# Bandage_FPC.net
KiCad netlist of a schematic drawn in EAGLE
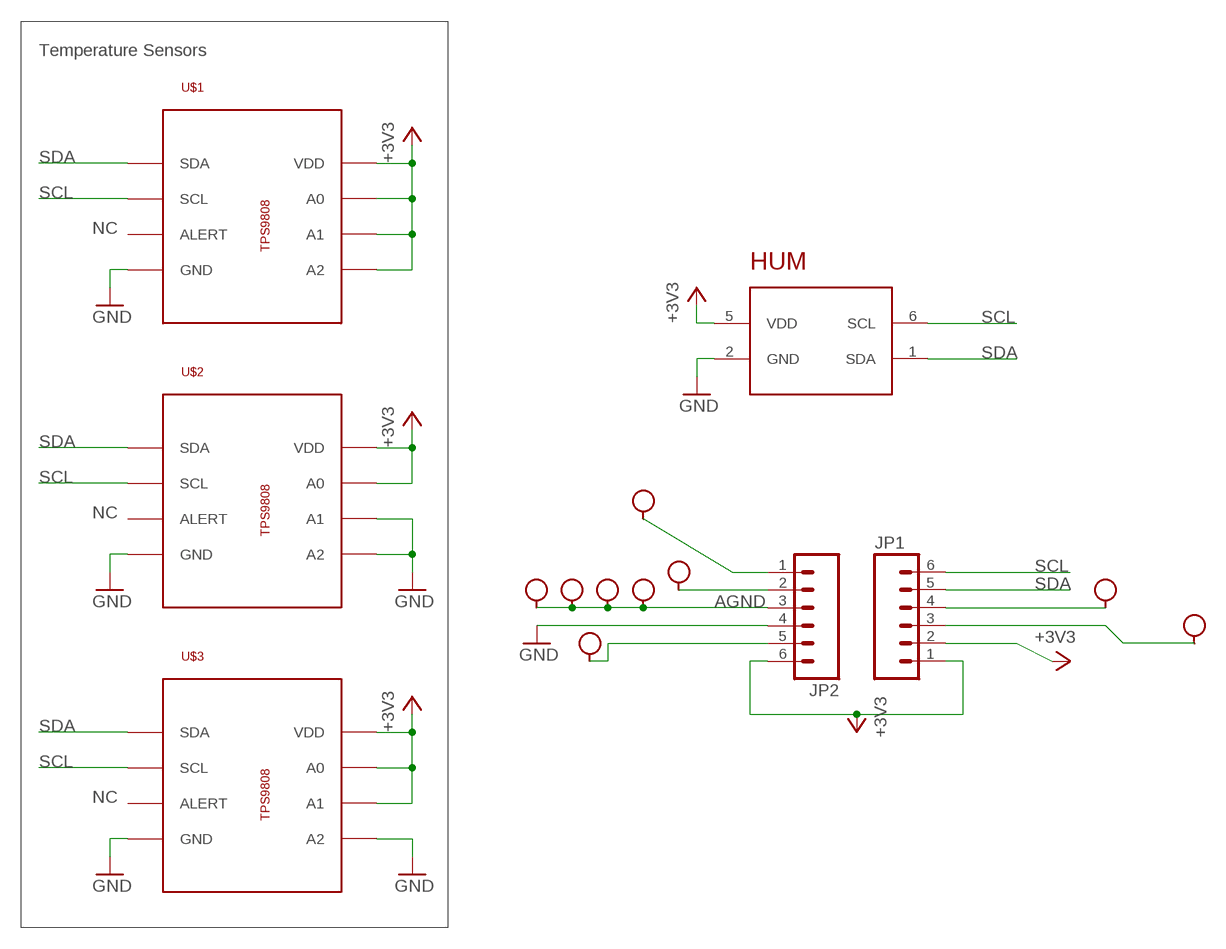
[diagram p0: schematic, sheet 1]

(export (version "E")
  (design (tool "Eeschema 10.0.6"))
  (components
    (comp (ref "H1")
      (value "SEW_HOLE-SMALL")
      (footprint "eagle-import:SIMPLE_HOLE_SM")
      (libsource (lib "eagle-import") (part "SEW_HOLE-SMALL"))
    )
    (comp (ref "H2")
      (value "SEW_HOLE-SMALL")
      (footprint "eagle-import:SIMPLE_HOLE_SM")
      (libsource (lib "eagle-import") (part "SEW_HOLE-SMALL"))
    )
    (comp (ref "H3")
      (value "SEW_HOLE-SMALL")
      (footprint "eagle-import:SIMPLE_HOLE_SM")
      (libsource (lib "eagle-import") (part "SEW_HOLE-SMALL"))
    )
    (comp (ref "H4")
      (value "SEW_HOLE-SMALL")
      (footprint "eagle-import:SIMPLE_HOLE_SM")
      (libsource (lib "eagle-import") (part "SEW_HOLE-SMALL"))
    )
    (comp (ref "H5")
      (value "SEW_HOLE-SMALL")
      (footprint "eagle-import:SIMPLE_HOLE_SM")
      (libsource (lib "eagle-import") (part "SEW_HOLE-SMALL"))
    )
    (comp (ref "H6")
      (value "SEW_HOLE-SMALL")
      (footprint "eagle-import:SIMPLE_HOLE_SM")
      (libsource (lib "eagle-import") (part "SEW_HOLE-SMALL"))
    )
    (comp (ref "H7")
      (value "SEW_HOLE-SMALL")
      (footprint "eagle-import:SIMPLE_HOLE_SM")
      (libsource (lib "eagle-import") (part "SEW_HOLE-SMALL"))
    )
    (comp (ref "H8")
      (value "SEW_HOLE-SMALL")
      (footprint "eagle-import:SIMPLE_HOLE_SM")
      (libsource (lib "eagle-import") (part "SEW_HOLE-SMALL"))
    )
    (comp (ref "H9")
      (value "SEW_HOLE-SMALL")
      (footprint "eagle-import:SIMPLE_HOLE_SM")
      (libsource (lib "eagle-import") (part "SEW_HOLE-SMALL"))
    )
    (comp (ref "HUM")
      (value "HDC1050")
      (footprint "eagle-import:SON-6")
      (libsource (lib "eagle-import") (part "HDC1050"))
    )
    (comp (ref "JP1")
      (value "M06LOCK")
      (footprint "eagle-import:1X06_LOCK")
      (libsource (lib "eagle-import") (part "M06LOCK"))
    )
    (comp (ref "JP2")
      (value "M06LOCK")
      (footprint "eagle-import:1X06_LOCK")
      (libsource (lib "eagle-import") (part "M06LOCK"))
    )
    (comp (ref "U$1")
      (value "MCP9808")
      (footprint "eagle-import:MSOP8")
      (libsource (lib "eagle-import") (part "MCP9808"))
    )
    (comp (ref "U$2")
      (value "MCP9808")
      (footprint "eagle-import:MSOP8")
      (libsource (lib "eagle-import") (part "MCP9808"))
    )
    (comp (ref "U$3")
      (value "MCP9808")
      (footprint "eagle-import:MSOP8")
      (libsource (lib "eagle-import") (part "MCP9808"))
    )
  )
  (nets
    (net (code "1") (name "+3V3") (class "Default")
      (node (ref "HUM") (pin "5") (pinfunction "VDD_5") (pintype "bidirectional"))
      (node (ref "JP1") (pin "1") (pinfunction "1_1") (pintype "passive"))
      (node (ref "JP1") (pin "2") (pinfunction "2_2") (pintype "passive"))
      (node (ref "JP2") (pin "6") (pinfunction "6_6") (pintype "passive"))
      (node (ref "U$1") (pin "5") (pinfunction "A2_5") (pintype "bidirectional"))
      (node (ref "U$1") (pin "6") (pinfunction "A1_6") (pintype "bidirectional"))
      (node (ref "U$1") (pin "7") (pinfunction "A0_7") (pintype "bidirectional"))
      (node (ref "U$1") (pin "8") (pinfunction "VDD_8") (pintype "bidirectional"))
      (node (ref "U$2") (pin "7") (pinfunction "A0_7") (pintype "bidirectional"))
      (node (ref "U$2") (pin "8") (pinfunction "VDD_8") (pintype "bidirectional"))
      (node (ref "U$3") (pin "6") (pinfunction "A1_6") (pintype "bidirectional"))
      (node (ref "U$3") (pin "7") (pinfunction "A0_7") (pintype "bidirectional"))
      (node (ref "U$3") (pin "8") (pinfunction "VDD_8") (pintype "bidirectional"))
    )
    (net (code "2") (name "/AGND") (class "Default")
      (node (ref "H6") (pin "P$1") (pinfunction "P$1_P$1") (pintype "bidirectional"))
      (node (ref "H7") (pin "P$1") (pinfunction "P$1_P$1") (pintype "bidirectional"))
      (node (ref "H8") (pin "P$1") (pinfunction "P$1_P$1") (pintype "bidirectional"))
      (node (ref "H9") (pin "P$1") (pinfunction "P$1_P$1") (pintype "bidirectional"))
      (node (ref "JP2") (pin "3") (pinfunction "3_3") (pintype "passive"))
    )
    (net (code "3") (name "/SCL") (class "Default")
      (node (ref "HUM") (pin "6") (pinfunction "SCL_6") (pintype "bidirectional"))
      (node (ref "JP1") (pin "6") (pinfunction "6_6") (pintype "passive"))
      (node (ref "U$1") (pin "2") (pinfunction "SCL_2") (pintype "bidirectional"))
      (node (ref "U$2") (pin "2") (pinfunction "SCL_2") (pintype "bidirectional"))
      (node (ref "U$3") (pin "2") (pinfunction "SCL_2") (pintype "bidirectional"))
    )
    (net (code "4") (name "/SDA") (class "Default")
      (node (ref "HUM") (pin "1") (pinfunction "SDA_1") (pintype "bidirectional"))
      (node (ref "JP1") (pin "5") (pinfunction "5_5") (pintype "passive"))
      (node (ref "U$1") (pin "1") (pinfunction "SDA_1") (pintype "bidirectional"))
      (node (ref "U$2") (pin "1") (pinfunction "SDA_1") (pintype "bidirectional"))
      (node (ref "U$3") (pin "1") (pinfunction "SDA_1") (pintype "bidirectional"))
    )
    (net (code "5") (name "GND") (class "Default")
      (node (ref "HUM") (pin "2") (pinfunction "GND_2") (pintype "bidirectional"))
      (node (ref "JP2") (pin "4") (pinfunction "4_4") (pintype "passive"))
      (node (ref "U$1") (pin "4") (pinfunction "GND_4") (pintype "bidirectional"))
      (node (ref "U$2") (pin "4") (pinfunction "GND_4") (pintype "bidirectional"))
      (node (ref "U$2") (pin "5") (pinfunction "A2_5") (pintype "bidirectional"))
      (node (ref "U$2") (pin "6") (pinfunction "A1_6") (pintype "bidirectional"))
      (node (ref "U$3") (pin "4") (pinfunction "GND_4") (pintype "bidirectional"))
      (node (ref "U$3") (pin "5") (pinfunction "A2_5") (pintype "bidirectional"))
    )
    (net (code "6") (name "Net-(H1-PadP$1)") (class "Default")
      (node (ref "H1") (pin "P$1") (pinfunction "P$1_P$1") (pintype "bidirectional"))
      (node (ref "JP2") (pin "5") (pinfunction "5_5") (pintype "passive"))
    )
    (net (code "7") (name "Net-(H2-PadP$1)") (class "Default")
      (node (ref "H2") (pin "P$1") (pinfunction "P$1_P$1") (pintype "bidirectional"))
      (node (ref "JP1") (pin "3") (pinfunction "3_3") (pintype "passive"))
    )
    (net (code "8") (name "Net-(H3-PadP$1)") (class "Default")
      (node (ref "H3") (pin "P$1") (pinfunction "P$1_P$1") (pintype "bidirectional"))
      (node (ref "JP1") (pin "4") (pinfunction "4_4") (pintype "passive"))
    )
    (net (code "9") (name "Net-(H4-PadP$1)") (class "Default")
      (node (ref "H4") (pin "P$1") (pinfunction "P$1_P$1") (pintype "bidirectional"))
      (node (ref "JP2") (pin "2") (pinfunction "2_2") (pintype "passive"))
    )
    (net (code "10") (name "Net-(H5-PadP$1)") (class "Default")
      (node (ref "H5") (pin "P$1") (pinfunction "P$1_P$1") (pintype "bidirectional"))
      (node (ref "JP2") (pin "1") (pinfunction "1_1") (pintype "passive"))
    )
    (net (code "11") (name "unconnected-(U$1-ALERT-Pad3)") (class "Default")
      (node (ref "U$1") (pin "3") (pinfunction "ALERT_3") (pintype "bidirectional"))
    )
    (net (code "12") (name "unconnected-(U$2-ALERT-Pad3)") (class "Default")
      (node (ref "U$2") (pin "3") (pinfunction "ALERT_3") (pintype "bidirectional"))
    )
    (net (code "13") (name "unconnected-(U$3-ALERT-Pad3)") (class "Default")
      (node (ref "U$3") (pin "3") (pinfunction "ALERT_3") (pintype "bidirectional"))
    )
  )
)
